# ServoBoard.net
KiCad netlist of a schematic drawn in EAGLE
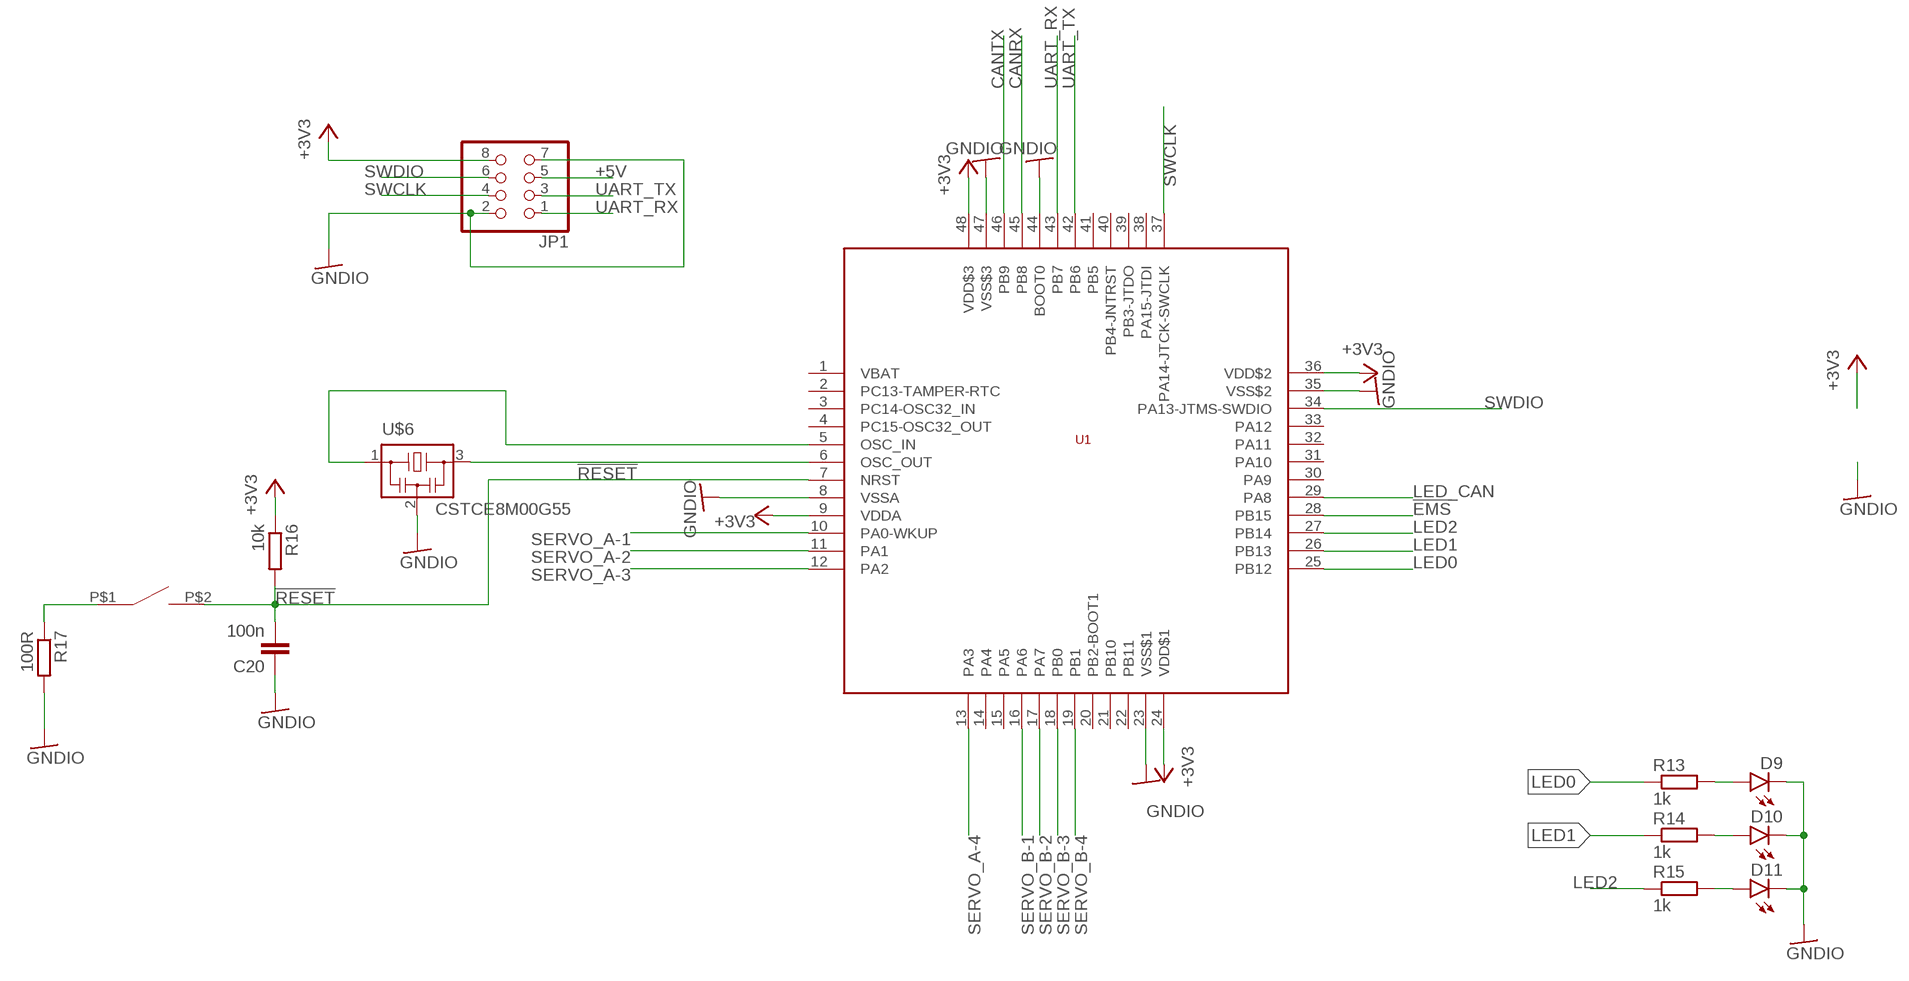
[diagram p0: schematic, sheet 1]
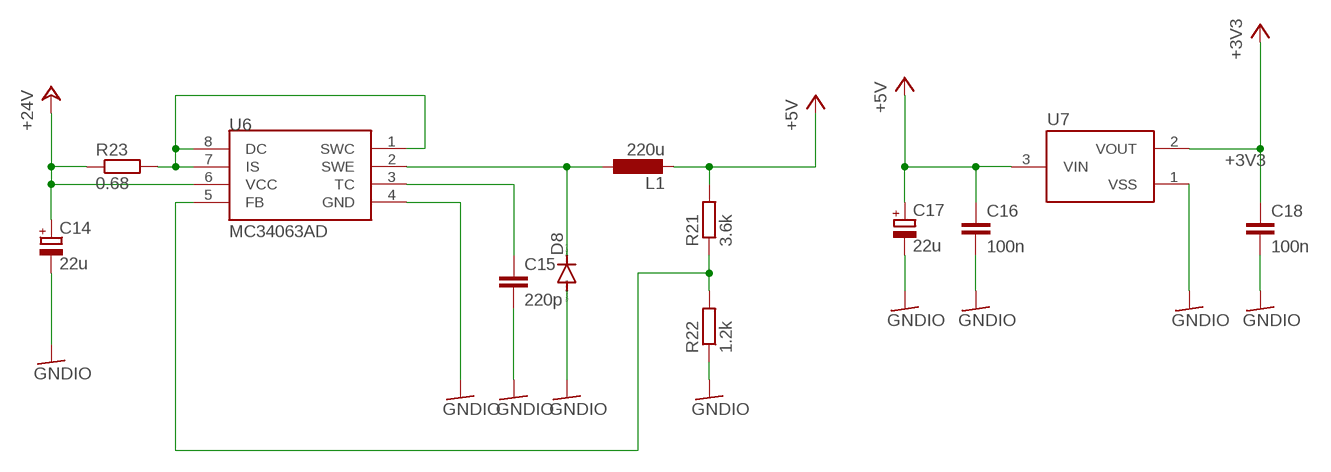
[diagram p1: schematic, sheet 2]
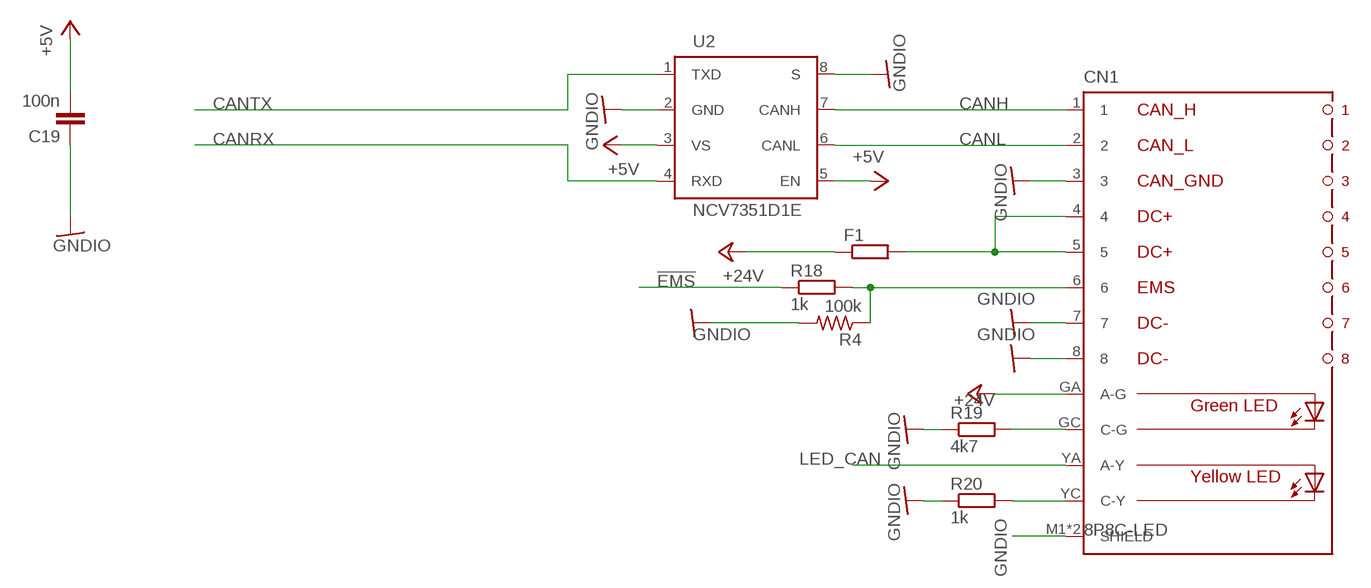
[diagram p2: schematic, sheet 3]
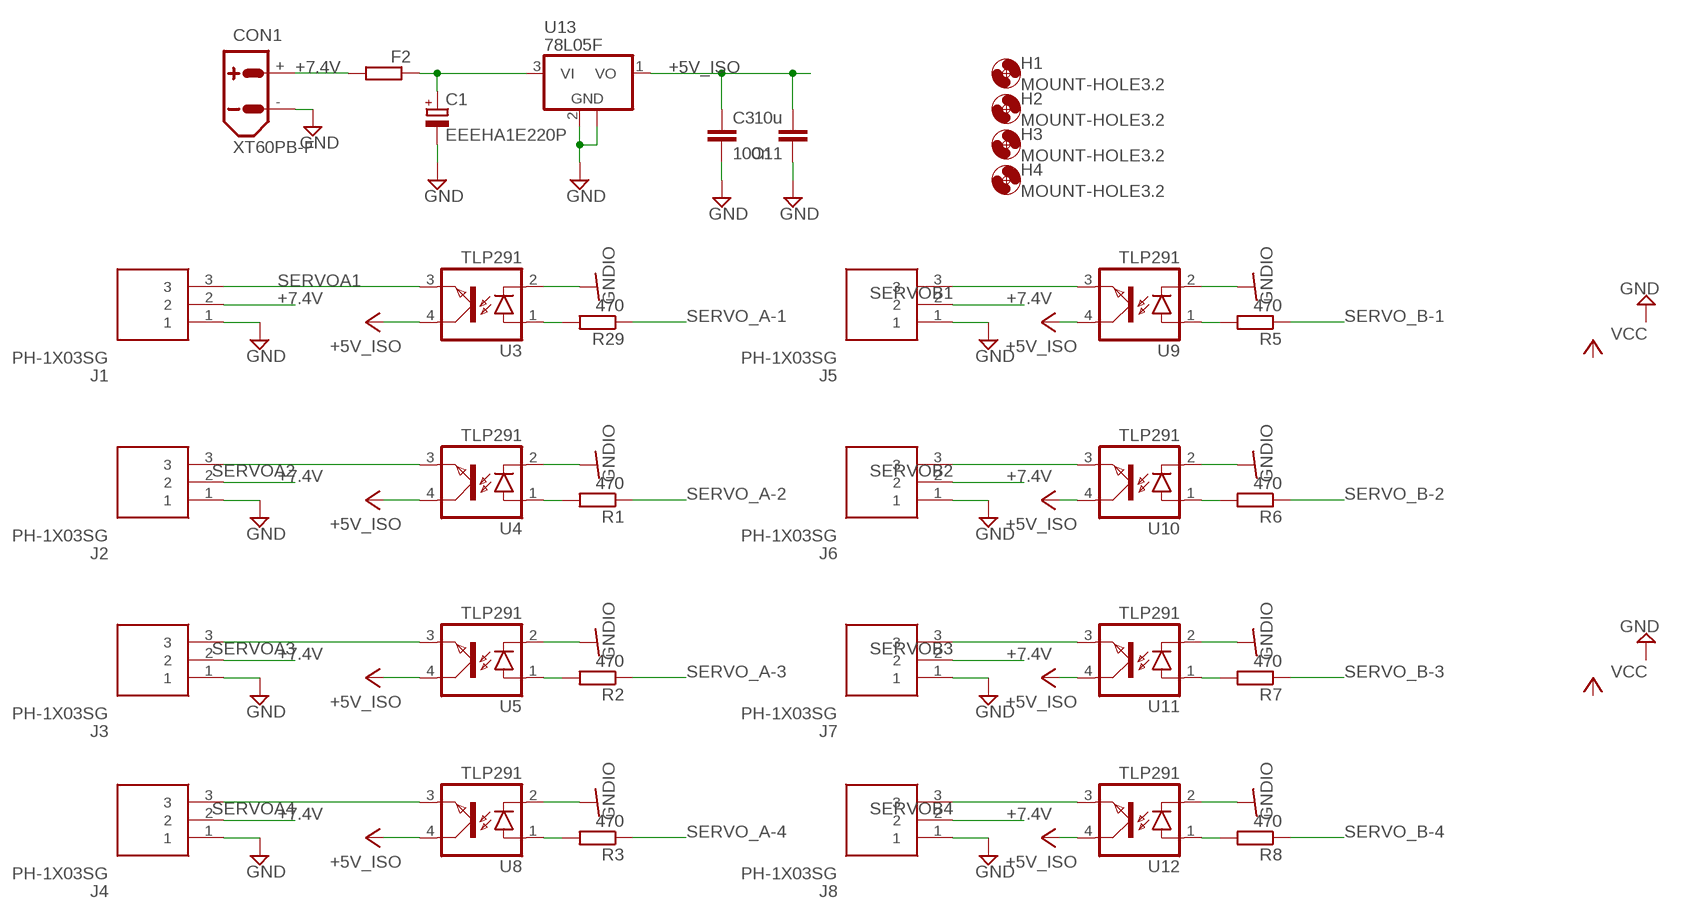
[diagram p3: schematic, sheet 4]

(export (version "E")
  (design (tool "Eeschema 10.0.6"))
  (components
    (comp (ref "C20")
      (value "100n")
      (footprint "eagle-import:C0603")
      (libsource (lib "eagle-import") (part "C-EUC0603"))
    )
    (comp (ref "D9")
      (value "LEDCHIPLED_0805")
      (footprint "eagle-import:CHIPLED_0805")
      (libsource (lib "eagle-import") (part "LEDCHIPLED_0805"))
    )
    (comp (ref "D10")
      (value "LEDCHIPLED_0805")
      (footprint "eagle-import:CHIPLED_0805")
      (libsource (lib "eagle-import") (part "LEDCHIPLED_0805"))
    )
    (comp (ref "D11")
      (value "LEDCHIPLED_0805")
      (footprint "eagle-import:CHIPLED_0805")
      (libsource (lib "eagle-import") (part "LEDCHIPLED_0805"))
    )
    (comp (ref "JP1")
      (value "PINHD-2X4")
      (footprint "eagle-import:2X04")
      (libsource (lib "eagle-import") (part "PINHD-2X4"))
    )
    (comp (ref "R13")
      (value "1k")
      (footprint "eagle-import:R0603")
      (libsource (lib "eagle-import") (part "R-EU_R0603"))
    )
    (comp (ref "R14")
      (value "1k")
      (footprint "eagle-import:R0603")
      (libsource (lib "eagle-import") (part "R-EU_R0603"))
    )
    (comp (ref "R15")
      (value "1k")
      (footprint "eagle-import:R0603")
      (libsource (lib "eagle-import") (part "R-EU_R0603"))
    )
    (comp (ref "R16")
      (value "10k")
      (footprint "eagle-import:R0603")
      (libsource (lib "eagle-import") (part "R-EU_R0603"))
    )
    (comp (ref "R17")
      (value "100R")
      (footprint "eagle-import:R0603")
      (libsource (lib "eagle-import") (part "R-EU_R0603"))
    )
    (comp (ref "SW1")
      (value "SWITCH_TACTILETOP")
      (footprint "eagle-import:SWITCH_TACTILE_3X6")
      (libsource (lib "eagle-import") (part "SWITCH_TACTILETOP"))
    )
    (comp (ref "U$6")
      (value "CSTCE8M00G55")
      (footprint "eagle-import:CSTCE8M00G55")
      (libsource (lib "eagle-import") (part "CSTCE8M00G55"))
    )
    (comp (ref "U1")
      (value "STM32F103C8")
      (footprint "eagle-import:LQFP48")
      (libsource (lib "eagle-import") (part "STM32F103C8"))
    )
    (comp (ref "C19")
      (value "100n")
      (footprint "eagle-import:C0603")
      (libsource (lib "eagle-import") (part "C-EUC0603"))
    )
    (comp (ref "CN1")
      (value "8P8C-LED")
      (footprint "eagle-import:8P8C-LED")
      (libsource (lib "eagle-import") (part "8P8C-LED"))
    )
    (comp (ref "F1")
      (value "R-EU_R1206")
      (footprint "eagle-import:R1206")
      (libsource (lib "eagle-import") (part "rcl_334_R-EU_R1206"))
    )
    (comp (ref "R4")
      (value "100k")
      (footprint "eagle-import:R0603")
      (libsource (lib "eagle-import") (part "R-US_R0603"))
    )
    (comp (ref "R18")
      (value "1k")
      (footprint "eagle-import:R0603")
      (libsource (lib "eagle-import") (part "rcl_334_R-EU_R0603"))
    )
    (comp (ref "R19")
      (value "4k7")
      (footprint "eagle-import:R0603")
      (libsource (lib "eagle-import") (part "rcl_334_R-EU_R0603"))
    )
    (comp (ref "R20")
      (value "1k")
      (footprint "eagle-import:R0603")
      (libsource (lib "eagle-import") (part "rcl_334_R-EU_R0603"))
    )
    (comp (ref "U2")
      (value "NCV7351D1E")
      (footprint "eagle-import:SO08")
      (libsource (lib "eagle-import") (part "NCV7351D1E"))
    )
    (comp (ref "C1")
      (value "EEEHA1E220P")
      (footprint "eagle-import:153CLV-0605")
      (libsource (lib "eagle-import") (part "rcl_334_CPOL-EU153CLV-0605"))
    )
    (comp (ref "C3")
      (value "100n")
      (footprint "eagle-import:C0603")
      (libsource (lib "eagle-import") (part "rcl_334_C-EUC0603"))
    )
    (comp (ref "C11")
      (value "10u")
      (footprint "eagle-import:C1210")
      (libsource (lib "eagle-import") (part "rcl_334_C-EUC1210"))
    )
    (comp (ref "CON1")
      (value "XT60PB-F")
      (footprint "eagle-import:XT60PB-F")
      (libsource (lib "eagle-import") (part "XT60PB-F"))
    )
    (comp (ref "F2")
      (value "R-EU_R1206")
      (footprint "eagle-import:R1206")
      (libsource (lib "eagle-import") (part "rcl_334_R-EU_R1206"))
    )
    (comp (ref "H1")
      (value "MOUNT-HOLE3.2")
      (footprint "eagle-import:3,2")
      (libsource (lib "eagle-import") (part "MOUNT-HOLE3.2"))
    )
    (comp (ref "H2")
      (value "MOUNT-HOLE3.2")
      (footprint "eagle-import:3,2")
      (libsource (lib "eagle-import") (part "MOUNT-HOLE3.2"))
    )
    (comp (ref "H3")
      (value "MOUNT-HOLE3.2")
      (footprint "eagle-import:3,2")
      (libsource (lib "eagle-import") (part "MOUNT-HOLE3.2"))
    )
    (comp (ref "H4")
      (value "MOUNT-HOLE3.2")
      (footprint "eagle-import:3,2")
      (libsource (lib "eagle-import") (part "MOUNT-HOLE3.2"))
    )
    (comp (ref "J1")
      (value "PH-1X03SG")
      (footprint "eagle-import:HDRV3W66P254_1X3_762X250X895P")
      (libsource (lib "eagle-import") (part "PH-1X03SG"))
    )
    (comp (ref "J2")
      (value "PH-1X03SG")
      (footprint "eagle-import:HDRV3W66P254_1X3_762X250X895P")
      (libsource (lib "eagle-import") (part "PH-1X03SG"))
    )
    (comp (ref "J3")
      (value "PH-1X03SG")
      (footprint "eagle-import:HDRV3W66P254_1X3_762X250X895P")
      (libsource (lib "eagle-import") (part "PH-1X03SG"))
    )
    (comp (ref "J4")
      (value "PH-1X03SG")
      (footprint "eagle-import:HDRV3W66P254_1X3_762X250X895P")
      (libsource (lib "eagle-import") (part "PH-1X03SG"))
    )
    (comp (ref "J5")
      (value "PH-1X03SG")
      (footprint "eagle-import:HDRV3W66P254_1X3_762X250X895P")
      (libsource (lib "eagle-import") (part "PH-1X03SG"))
    )
    (comp (ref "J6")
      (value "PH-1X03SG")
      (footprint "eagle-import:HDRV3W66P254_1X3_762X250X895P")
      (libsource (lib "eagle-import") (part "PH-1X03SG"))
    )
    (comp (ref "J7")
      (value "PH-1X03SG")
      (footprint "eagle-import:HDRV3W66P254_1X3_762X250X895P")
      (libsource (lib "eagle-import") (part "PH-1X03SG"))
    )
    (comp (ref "J8")
      (value "PH-1X03SG")
      (footprint "eagle-import:HDRV3W66P254_1X3_762X250X895P")
      (libsource (lib "eagle-import") (part "PH-1X03SG"))
    )
    (comp (ref "R1")
      (value "470")
      (footprint "eagle-import:R0603")
      (libsource (lib "eagle-import") (part "rcl_334_R-EU_R0603"))
    )
    (comp (ref "R2")
      (value "470")
      (footprint "eagle-import:R0603")
      (libsource (lib "eagle-import") (part "rcl_334_R-EU_R0603"))
    )
    (comp (ref "R3")
      (value "470")
      (footprint "eagle-import:R0603")
      (libsource (lib "eagle-import") (part "rcl_334_R-EU_R0603"))
    )
    (comp (ref "R5")
      (value "470")
      (footprint "eagle-import:R0603")
      (libsource (lib "eagle-import") (part "rcl_334_R-EU_R0603"))
    )
    (comp (ref "R6")
      (value "470")
      (footprint "eagle-import:R0603")
      (libsource (lib "eagle-import") (part "rcl_334_R-EU_R0603"))
    )
    (comp (ref "R7")
      (value "470")
      (footprint "eagle-import:R0603")
      (libsource (lib "eagle-import") (part "rcl_334_R-EU_R0603"))
    )
    (comp (ref "R8")
      (value "470")
      (footprint "eagle-import:R0603")
      (libsource (lib "eagle-import") (part "rcl_334_R-EU_R0603"))
    )
    (comp (ref "R29")
      (value "470")
      (footprint "eagle-import:R0603")
      (libsource (lib "eagle-import") (part "rcl_334_R-EU_R0603"))
    )
    (comp (ref "U3")
      (value "TLP291")
      (footprint "eagle-import:MINI-FLAT-4")
      (libsource (lib "eagle-import") (part "TLP291"))
    )
    (comp (ref "U4")
      (value "TLP291")
      (footprint "eagle-import:MINI-FLAT-4")
      (libsource (lib "eagle-import") (part "TLP291"))
    )
    (comp (ref "U5")
      (value "TLP291")
      (footprint "eagle-import:MINI-FLAT-4")
      (libsource (lib "eagle-import") (part "TLP291"))
    )
    (comp (ref "U8")
      (value "TLP291")
      (footprint "eagle-import:MINI-FLAT-4")
      (libsource (lib "eagle-import") (part "TLP291"))
    )
    (comp (ref "U9")
      (value "TLP291")
      (footprint "eagle-import:MINI-FLAT-4")
      (libsource (lib "eagle-import") (part "TLP291"))
    )
    (comp (ref "U10")
      (value "TLP291")
      (footprint "eagle-import:MINI-FLAT-4")
      (libsource (lib "eagle-import") (part "TLP291"))
    )
    (comp (ref "U11")
      (value "TLP291")
      (footprint "eagle-import:MINI-FLAT-4")
      (libsource (lib "eagle-import") (part "TLP291"))
    )
    (comp (ref "U12")
      (value "TLP291")
      (footprint "eagle-import:MINI-FLAT-4")
      (libsource (lib "eagle-import") (part "TLP291"))
    )
    (comp (ref "U13")
      (value "78L05F")
      (footprint "eagle-import:SOT89")
      (libsource (lib "eagle-import") (part "78LF05"))
    )
    (comp (ref "C14")
      (value "22u")
      (footprint "eagle-import:E2-5")
      (libsource (lib "eagle-import") (part "CPOL-EUE2-5"))
    )
    (comp (ref "C15")
      (value "220p")
      (footprint "eagle-import:C0603")
      (libsource (lib "eagle-import") (part "rcl_334_C-EUC0603"))
    )
    (comp (ref "C16")
      (value "100n")
      (footprint "eagle-import:C0603")
      (libsource (lib "eagle-import") (part "C-EUC0603"))
    )
    (comp (ref "C17")
      (value "22u")
      (footprint "eagle-import:E2-5")
      (libsource (lib "eagle-import") (part "CPOL-EUE2-5"))
    )
    (comp (ref "C18")
      (value "100n")
      (footprint "eagle-import:C0603")
      (libsource (lib "eagle-import") (part "C-EUC0603"))
    )
    (comp (ref "D8")
      (value "DIODE-SOD123")
      (footprint "eagle-import:SOD123")
      (libsource (lib "eagle-import") (part "DIODE-SOD123"))
    )
    (comp (ref "L1")
      (value "220u")
      (footprint "eagle-import:L5852")
      (libsource (lib "eagle-import") (part "L5852"))
    )
    (comp (ref "R21")
      (value "3.6k")
      (footprint "eagle-import:R0603")
      (libsource (lib "eagle-import") (part "rcl_334_R-EU_R0603"))
    )
    (comp (ref "R22")
      (value "1.2k")
      (footprint "eagle-import:R0603")
      (libsource (lib "eagle-import") (part "rcl_334_R-EU_R0603"))
    )
    (comp (ref "R23")
      (value "0.68")
      (footprint "eagle-import:R1206")
      (libsource (lib "eagle-import") (part "rcl_334_R-EU_R1206"))
    )
    (comp (ref "U6")
      (value "MC34063AD")
      (footprint "eagle-import:SOIC8")
      (libsource (lib "eagle-import") (part "MC34063AD"))
    )
    (comp (ref "U7")
      (value "XC6206")
      (footprint "eagle-import:SOT95P240X110-3")
      (libsource (lib "eagle-import") (part "XC6206"))
    )
  )
  (nets
    (net (code "1") (name "+3V3") (class "Default")
      (node (ref "C18") (pin "1") (pinfunction "1_1") (pintype "passive"))
      (node (ref "JP1") (pin "8") (pinfunction "8_8") (pintype "passive"))
      (node (ref "R16") (pin "1") (pinfunction "1_1") (pintype "passive"))
      (node (ref "U1") (pin "24") (pinfunction "VDD$1_24") (pintype "passive"))
      (node (ref "U1") (pin "36") (pinfunction "VDD$2_36") (pintype "passive"))
      (node (ref "U1") (pin "48") (pinfunction "VDD$3_48") (pintype "passive"))
      (node (ref "U1") (pin "9") (pinfunction "VDDA_9") (pintype "bidirectional"))
      (node (ref "U7") (pin "2") (pinfunction "VOUT_2") (pintype "bidirectional"))
    )
    (net (code "2") (name "+5V") (class "Default")
      (node (ref "C16") (pin "1") (pinfunction "1_1") (pintype "passive"))
      (node (ref "C17") (pin "+") (pinfunction "+_+") (pintype "passive"))
      (node (ref "C19") (pin "2") (pinfunction "2_2") (pintype "passive"))
      (node (ref "JP1") (pin "5") (pinfunction "5_5") (pintype "passive"))
      (node (ref "L1") (pin "P$2") (pinfunction "2_P$2") (pintype "passive"))
      (node (ref "R21") (pin "2") (pinfunction "2_2") (pintype "passive"))
      (node (ref "U2") (pin "3") (pinfunction "VS_3") (pintype "power_in"))
      (node (ref "U2") (pin "5") (pinfunction "EN_5") (pintype "input"))
      (node (ref "U7") (pin "3") (pinfunction "VIN_3") (pintype "bidirectional"))
    )
    (net (code "3") (name "+5V_ISO") (class "Default")
      (node (ref "C11") (pin "2") (pinfunction "2_2") (pintype "passive"))
      (node (ref "C3") (pin "1") (pinfunction "1_1") (pintype "passive"))
      (node (ref "U10") (pin "4") (pinfunction "COL_4") (pintype "passive"))
      (node (ref "U11") (pin "4") (pinfunction "COL_4") (pintype "passive"))
      (node (ref "U12") (pin "4") (pinfunction "COL_4") (pintype "passive"))
      (node (ref "U13") (pin "1") (pinfunction "VO_1") (pintype "passive"))
      (node (ref "U3") (pin "4") (pinfunction "COL_4") (pintype "passive"))
      (node (ref "U4") (pin "4") (pinfunction "COL_4") (pintype "passive"))
      (node (ref "U5") (pin "4") (pinfunction "COL_4") (pintype "passive"))
      (node (ref "U8") (pin "4") (pinfunction "COL_4") (pintype "passive"))
      (node (ref "U9") (pin "4") (pinfunction "COL_4") (pintype "passive"))
    )
    (net (code "4") (name "+7.4V") (class "Default")
      (node (ref "CON1") (pin "+") (pinfunction "+_+") (pintype "power_in"))
      (node (ref "F2") (pin "2") (pinfunction "2_2") (pintype "passive"))
      (node (ref "J1") (pin "2") (pinfunction "2_2") (pintype "bidirectional"))
      (node (ref "J2") (pin "2") (pinfunction "2_2") (pintype "bidirectional"))
      (node (ref "J3") (pin "2") (pinfunction "2_2") (pintype "bidirectional"))
      (node (ref "J4") (pin "2") (pinfunction "2_2") (pintype "bidirectional"))
      (node (ref "J5") (pin "2") (pinfunction "2_2") (pintype "bidirectional"))
      (node (ref "J6") (pin "2") (pinfunction "2_2") (pintype "bidirectional"))
      (node (ref "J7") (pin "2") (pinfunction "2_2") (pintype "bidirectional"))
      (node (ref "J8") (pin "2") (pinfunction "2_2") (pintype "bidirectional"))
    )
    (net (code "5") (name "+24V") (class "Default")
      (node (ref "C14") (pin "+") (pinfunction "+_+") (pintype "passive"))
      (node (ref "CN1") (pin "GA") (pinfunction "A-G_GA") (pintype "passive"))
      (node (ref "F1") (pin "1") (pinfunction "1_1") (pintype "passive"))
      (node (ref "R23") (pin "1") (pinfunction "1_1") (pintype "passive"))
      (node (ref "U6") (pin "6") (pinfunction "VCC_6") (pintype "passive"))
    )
    (net (code "6") (name "CANH") (class "Default")
      (node (ref "CN1") (pin "1") (pinfunction "1_1") (pintype "input"))
      (node (ref "U2") (pin "7") (pinfunction "CANH_7") (pintype "output"))
    )
    (net (code "7") (name "CANL") (class "Default")
      (node (ref "CN1") (pin "2") (pinfunction "2_2") (pintype "input"))
      (node (ref "U2") (pin "6") (pinfunction "CANL_6") (pintype "output"))
    )
    (net (code "8") (name "CANRX") (class "Default")
      (node (ref "U1") (pin "45") (pinfunction "PB8_45") (pintype "bidirectional"))
      (node (ref "U2") (pin "4") (pinfunction "RXD_4") (pintype "output"))
    )
    (net (code "9") (name "CANTX") (class "Default")
      (node (ref "U1") (pin "46") (pinfunction "PB9_46") (pintype "bidirectional"))
      (node (ref "U2") (pin "1") (pinfunction "TXD_1") (pintype "input"))
    )
    (net (code "10") (name "GND") (class "Default")
      (node (ref "C1") (pin "-") (pinfunction "-_-") (pintype "passive"))
      (node (ref "C11") (pin "1") (pinfunction "1_1") (pintype "passive"))
      (node (ref "C3") (pin "2") (pinfunction "2_2") (pintype "passive"))
      (node (ref "CON1") (pin "-") (pinfunction "-_-") (pintype "power_in"))
      (node (ref "J1") (pin "1") (pinfunction "1_1") (pintype "bidirectional"))
      (node (ref "J2") (pin "1") (pinfunction "1_1") (pintype "bidirectional"))
      (node (ref "J3") (pin "1") (pinfunction "1_1") (pintype "bidirectional"))
      (node (ref "J4") (pin "1") (pinfunction "1_1") (pintype "bidirectional"))
      (node (ref "J5") (pin "1") (pinfunction "1_1") (pintype "bidirectional"))
      (node (ref "J6") (pin "1") (pinfunction "1_1") (pintype "bidirectional"))
      (node (ref "J7") (pin "1") (pinfunction "1_1") (pintype "bidirectional"))
      (node (ref "J8") (pin "1") (pinfunction "1_1") (pintype "bidirectional"))
      (node (ref "U13") (pin "2") (pinfunction "GND_2") (pintype "passive"))
      (node (ref "U13") (pin "2@1") (pinfunction "GND_2@1") (pintype "passive"))
    )
    (net (code "11") (name "GNDIO") (class "Default")
      (node (ref "C14") (pin "-") (pinfunction "-_-") (pintype "passive"))
      (node (ref "C15") (pin "2") (pinfunction "2_2") (pintype "passive"))
      (node (ref "C16") (pin "2") (pinfunction "2_2") (pintype "passive"))
      (node (ref "C17") (pin "-") (pinfunction "-_-") (pintype "passive"))
      (node (ref "C18") (pin "2") (pinfunction "2_2") (pintype "passive"))
      (node (ref "C19") (pin "1") (pinfunction "1_1") (pintype "passive"))
      (node (ref "C20") (pin "1") (pinfunction "1_1") (pintype "passive"))
      (node (ref "CN1") (pin "3") (pinfunction "3_3") (pintype "input"))
      (node (ref "CN1") (pin "7") (pinfunction "7_7") (pintype "input"))
      (node (ref "CN1") (pin "8") (pinfunction "8_8") (pintype "input"))
      (node (ref "CN1") (pin "M1") (pinfunction "SHIELD_M1") (pintype "passive"))
      (node (ref "CN1") (pin "M2") (pinfunction "SHIELD_M2") (pintype "passive"))
      (node (ref "D10") (pin "C") (pinfunction "C_C") (pintype "passive"))
      (node (ref "D11") (pin "C") (pinfunction "C_C") (pintype "passive"))
      (node (ref "D8") (pin "A") (pinfunction "A_A") (pintype "passive"))
      (node (ref "D9") (pin "C") (pinfunction "C_C") (pintype "passive"))
      (node (ref "JP1") (pin "2") (pinfunction "2_2") (pintype "passive"))
      (node (ref "JP1") (pin "7") (pinfunction "7_7") (pintype "passive"))
      (node (ref "R17") (pin "2") (pinfunction "2_2") (pintype "passive"))
      (node (ref "R19") (pin "1") (pinfunction "1_1") (pintype "passive"))
      (node (ref "R20") (pin "1") (pinfunction "1_1") (pintype "passive"))
      (node (ref "R22") (pin "1") (pinfunction "1_1") (pintype "passive"))
      (node (ref "R4") (pin "2") (pinfunction "2_2") (pintype "passive"))
      (node (ref "U$6") (pin "2") (pinfunction "2_2") (pintype "passive"))
      (node (ref "U1") (pin "23") (pinfunction "VSS$1_23") (pintype "passive"))
      (node (ref "U1") (pin "35") (pinfunction "VSS$2_35") (pintype "passive"))
      (node (ref "U1") (pin "44") (pinfunction "BOOT0_44") (pintype "input"))
      (node (ref "U1") (pin "47") (pinfunction "VSS$3_47") (pintype "passive"))
      (node (ref "U1") (pin "8") (pinfunction "VSSA_8") (pintype "bidirectional"))
      (node (ref "U10") (pin "2") (pinfunction "C_2") (pintype "passive"))
      (node (ref "U11") (pin "2") (pinfunction "C_2") (pintype "passive"))
      (node (ref "U12") (pin "2") (pinfunction "C_2") (pintype "passive"))
      (node (ref "U2") (pin "2") (pinfunction "GND_2") (pintype "power_in"))
      (node (ref "U2") (pin "8") (pinfunction "S_8") (pintype "input"))
      (node (ref "U3") (pin "2") (pinfunction "C_2") (pintype "passive"))
      (node (ref "U4") (pin "2") (pinfunction "C_2") (pintype "passive"))
      (node (ref "U5") (pin "2") (pinfunction "C_2") (pintype "passive"))
      (node (ref "U6") (pin "4") (pinfunction "GND_4") (pintype "passive"))
      (node (ref "U7") (pin "1") (pinfunction "VSS_1") (pintype "bidirectional"))
      (node (ref "U8") (pin "2") (pinfunction "C_2") (pintype "passive"))
      (node (ref "U9") (pin "2") (pinfunction "C_2") (pintype "passive"))
    )
    (net (code "12") (name "LED0") (class "Default")
      (node (ref "R13") (pin "1") (pinfunction "1_1") (pintype "passive"))
      (node (ref "U1") (pin "25") (pinfunction "PB12_25") (pintype "bidirectional"))
    )
    (net (code "13") (name "LED1") (class "Default")
      (node (ref "R14") (pin "1") (pinfunction "1_1") (pintype "passive"))
      (node (ref "U1") (pin "26") (pinfunction "PB13_26") (pintype "bidirectional"))
    )
    (net (code "14") (name "LED2") (class "Default")
      (node (ref "R15") (pin "1") (pinfunction "1_1") (pintype "passive"))
      (node (ref "U1") (pin "27") (pinfunction "PB14_27") (pintype "bidirectional"))
    )
    (net (code "15") (name "LED_CAN") (class "Default")
      (node (ref "CN1") (pin "YA") (pinfunction "A-Y_YA") (pintype "passive"))
      (node (ref "U1") (pin "29") (pinfunction "PA8_29") (pintype "bidirectional"))
    )
    (net (code "16") (name "Net-(CN1-C-G)") (class "Default")
      (node (ref "CN1") (pin "GC") (pinfunction "C-G_GC") (pintype "passive"))
      (node (ref "R19") (pin "2") (pinfunction "2_2") (pintype "passive"))
    )
    (net (code "17") (name "Net-(CN1-C-Y)") (class "Default")
      (node (ref "CN1") (pin "YC") (pinfunction "C-Y_YC") (pintype "passive"))
      (node (ref "R20") (pin "2") (pinfunction "2_2") (pintype "passive"))
    )
    (net (code "18") (name "Net-(CN1-Pad4)") (class "Default")
      (node (ref "CN1") (pin "4") (pinfunction "4_4") (pintype "input"))
      (node (ref "CN1") (pin "5") (pinfunction "5_5") (pintype "input"))
      (node (ref "F1") (pin "2") (pinfunction "2_2") (pintype "passive"))
    )
    (net (code "19") (name "Net-(CN1-Pad6)") (class "Default")
      (node (ref "CN1") (pin "6") (pinfunction "6_6") (pintype "input"))
      (node (ref "R18") (pin "2") (pinfunction "2_2") (pintype "passive"))
      (node (ref "R4") (pin "1") (pinfunction "1_1") (pintype "passive"))
    )
    (net (code "20") (name "Net-(D9-PadA)") (class "Default")
      (node (ref "D9") (pin "A") (pinfunction "A_A") (pintype "passive"))
      (node (ref "R13") (pin "2") (pinfunction "2_2") (pintype "passive"))
    )
    (net (code "21") (name "Net-(D10-PadA)") (class "Default")
      (node (ref "D10") (pin "A") (pinfunction "A_A") (pintype "passive"))
      (node (ref "R14") (pin "2") (pinfunction "2_2") (pintype "passive"))
    )
    (net (code "22") (name "Net-(D11-PadA)") (class "Default")
      (node (ref "D11") (pin "A") (pinfunction "A_A") (pintype "passive"))
      (node (ref "R15") (pin "2") (pinfunction "2_2") (pintype "passive"))
    )
    (net (code "23") (name "Net-(L1-1)") (class "Default")
      (node (ref "D8") (pin "C") (pinfunction "C_C") (pintype "passive"))
      (node (ref "L1") (pin "P$1") (pinfunction "1_P$1") (pintype "passive"))
      (node (ref "U6") (pin "2") (pinfunction "SWE_2") (pintype "passive"))
    )
    (net (code "24") (name "Net-(SW1-1)") (class "Default")
      (node (ref "R17") (pin "1") (pinfunction "1_1") (pintype "passive"))
      (node (ref "SW1") (pin "P$1") (pinfunction "1_P$1") (pintype "bidirectional"))
    )
    (net (code "25") (name "Net-(U1-OSC_IN)") (class "Default")
      (node (ref "U$6") (pin "1") (pinfunction "1_1") (pintype "passive"))
      (node (ref "U1") (pin "5") (pinfunction "OSC_IN_5") (pintype "input"))
    )
    (net (code "26") (name "Net-(U1-OSC_OUT)") (class "Default")
      (node (ref "U$6") (pin "3") (pinfunction "3_3") (pintype "passive"))
      (node (ref "U1") (pin "6") (pinfunction "OSC_OUT_6") (pintype "output"))
    )
    (net (code "27") (name "Net-(U3-A)") (class "Default")
      (node (ref "R29") (pin "2") (pinfunction "2_2") (pintype "passive"))
      (node (ref "U3") (pin "1") (pinfunction "A_1") (pintype "passive"))
    )
    (net (code "28") (name "Net-(U4-A)") (class "Default")
      (node (ref "R1") (pin "2") (pinfunction "2_2") (pintype "passive"))
      (node (ref "U4") (pin "1") (pinfunction "A_1") (pintype "passive"))
    )
    (net (code "29") (name "Net-(U5-A)") (class "Default")
      (node (ref "R2") (pin "2") (pinfunction "2_2") (pintype "passive"))
      (node (ref "U5") (pin "1") (pinfunction "A_1") (pintype "passive"))
    )
    (net (code "30") (name "Net-(U6-DC)") (class "Default")
      (node (ref "R23") (pin "2") (pinfunction "2_2") (pintype "passive"))
      (node (ref "U6") (pin "1") (pinfunction "SWC_1") (pintype "passive"))
      (node (ref "U6") (pin "7") (pinfunction "IS_7") (pintype "passive"))
      (node (ref "U6") (pin "8") (pinfunction "DC_8") (pintype "passive"))
    )
    (net (code "31") (name "Net-(U6-FB)") (class "Default")
      (node (ref "R21") (pin "1") (pinfunction "1_1") (pintype "passive"))
      (node (ref "R22") (pin "2") (pinfunction "2_2") (pintype "passive"))
      (node (ref "U6") (pin "5") (pinfunction "FB_5") (pintype "passive"))
    )
    (net (code "32") (name "Net-(U6-TC)") (class "Default")
      (node (ref "C15") (pin "1") (pinfunction "1_1") (pintype "passive"))
      (node (ref "U6") (pin "3") (pinfunction "TC_3") (pintype "passive"))
    )
    (net (code "33") (name "Net-(U8-A)") (class "Default")
      (node (ref "R3") (pin "2") (pinfunction "2_2") (pintype "passive"))
      (node (ref "U8") (pin "1") (pinfunction "A_1") (pintype "passive"))
    )
    (net (code "34") (name "Net-(U9-A)") (class "Default")
      (node (ref "R5") (pin "2") (pinfunction "2_2") (pintype "passive"))
      (node (ref "U9") (pin "1") (pinfunction "A_1") (pintype "passive"))
    )
    (net (code "35") (name "Net-(U10-A)") (class "Default")
      (node (ref "R6") (pin "2") (pinfunction "2_2") (pintype "passive"))
      (node (ref "U10") (pin "1") (pinfunction "A_1") (pintype "passive"))
    )
    (net (code "36") (name "Net-(U11-A)") (class "Default")
      (node (ref "R7") (pin "2") (pinfunction "2_2") (pintype "passive"))
      (node (ref "U11") (pin "1") (pinfunction "A_1") (pintype "passive"))
    )
    (net (code "37") (name "Net-(U12-A)") (class "Default")
      (node (ref "R8") (pin "2") (pinfunction "2_2") (pintype "passive"))
      (node (ref "U12") (pin "1") (pinfunction "A_1") (pintype "passive"))
    )
    (net (code "38") (name "Net-(U13-VI)") (class "Default")
      (node (ref "C1") (pin "+") (pinfunction "+_+") (pintype "passive"))
      (node (ref "F2") (pin "1") (pinfunction "1_1") (pintype "passive"))
      (node (ref "U13") (pin "3") (pinfunction "VI_3") (pintype "input"))
    )
    (net (code "39") (name "SERVOA1") (class "Default")
      (node (ref "J1") (pin "3") (pinfunction "3_3") (pintype "bidirectional"))
      (node (ref "U3") (pin "3") (pinfunction "EMIT_3") (pintype "passive"))
    )
    (net (code "40") (name "SERVOA2") (class "Default")
      (node (ref "J2") (pin "3") (pinfunction "3_3") (pintype "bidirectional"))
      (node (ref "U4") (pin "3") (pinfunction "EMIT_3") (pintype "passive"))
    )
    (net (code "41") (name "SERVOA3") (class "Default")
      (node (ref "J3") (pin "3") (pinfunction "3_3") (pintype "bidirectional"))
      (node (ref "U5") (pin "3") (pinfunction "EMIT_3") (pintype "passive"))
    )
    (net (code "42") (name "SERVOA4") (class "Default")
      (node (ref "J4") (pin "3") (pinfunction "3_3") (pintype "bidirectional"))
      (node (ref "U8") (pin "3") (pinfunction "EMIT_3") (pintype "passive"))
    )
    (net (code "43") (name "SERVOB1") (class "Default")
      (node (ref "J5") (pin "3") (pinfunction "3_3") (pintype "bidirectional"))
      (node (ref "U9") (pin "3") (pinfunction "EMIT_3") (pintype "passive"))
    )
    (net (code "44") (name "SERVOB2") (class "Default")
      (node (ref "J6") (pin "3") (pinfunction "3_3") (pintype "bidirectional"))
      (node (ref "U10") (pin "3") (pinfunction "EMIT_3") (pintype "passive"))
    )
    (net (code "45") (name "SERVOB3") (class "Default")
      (node (ref "J7") (pin "3") (pinfunction "3_3") (pintype "bidirectional"))
      (node (ref "U11") (pin "3") (pinfunction "EMIT_3") (pintype "passive"))
    )
    (net (code "46") (name "SERVOB4") (class "Default")
      (node (ref "J8") (pin "3") (pinfunction "3_3") (pintype "bidirectional"))
      (node (ref "U12") (pin "3") (pinfunction "EMIT_3") (pintype "passive"))
    )
    (net (code "47") (name "SERVO_A-1") (class "Default")
      (node (ref "R29") (pin "1") (pinfunction "1_1") (pintype "passive"))
      (node (ref "U1") (pin "10") (pinfunction "PA0-WKUP_10") (pintype "bidirectional"))
    )
    (net (code "48") (name "SERVO_A-2") (class "Default")
      (node (ref "R1") (pin "1") (pinfunction "1_1") (pintype "passive"))
      (node (ref "U1") (pin "11") (pinfunction "PA1_11") (pintype "bidirectional"))
    )
    (net (code "49") (name "SERVO_A-3") (class "Default")
      (node (ref "R2") (pin "1") (pinfunction "1_1") (pintype "passive"))
      (node (ref "U1") (pin "12") (pinfunction "PA2_12") (pintype "bidirectional"))
    )
    (net (code "50") (name "SERVO_A-4") (class "Default")
      (node (ref "R3") (pin "1") (pinfunction "1_1") (pintype "passive"))
      (node (ref "U1") (pin "13") (pinfunction "PA3_13") (pintype "bidirectional"))
    )
    (net (code "51") (name "SERVO_B-1") (class "Default")
      (node (ref "R5") (pin "1") (pinfunction "1_1") (pintype "passive"))
      (node (ref "U1") (pin "16") (pinfunction "PA6_16") (pintype "bidirectional"))
    )
    (net (code "52") (name "SERVO_B-2") (class "Default")
      (node (ref "R6") (pin "1") (pinfunction "1_1") (pintype "passive"))
      (node (ref "U1") (pin "17") (pinfunction "PA7_17") (pintype "bidirectional"))
    )
    (net (code "53") (name "SERVO_B-3") (class "Default")
      (node (ref "R7") (pin "1") (pinfunction "1_1") (pintype "passive"))
      (node (ref "U1") (pin "18") (pinfunction "PB0_18") (pintype "bidirectional"))
    )
    (net (code "54") (name "SERVO_B-4") (class "Default")
      (node (ref "R8") (pin "1") (pinfunction "1_1") (pintype "passive"))
      (node (ref "U1") (pin "19") (pinfunction "PB1_19") (pintype "bidirectional"))
    )
    (net (code "55") (name "SWCLK") (class "Default")
      (node (ref "JP1") (pin "4") (pinfunction "4_4") (pintype "passive"))
      (node (ref "U1") (pin "37") (pinfunction "PA14-JTCK-SWCLK_37") (pintype "bidirectional"))
    )
    (net (code "56") (name "SWDIO") (class "Default")
      (node (ref "JP1") (pin "6") (pinfunction "6_6") (pintype "passive"))
      (node (ref "U1") (pin "34") (pinfunction "PA13-JTMS-SWDIO_34") (pintype "bidirectional"))
    )
    (net (code "57") (name "UART_RX") (class "Default")
      (node (ref "JP1") (pin "1") (pinfunction "1_1") (pintype "passive"))
      (node (ref "U1") (pin "43") (pinfunction "PB7_43") (pintype "bidirectional"))
    )
    (net (code "58") (name "UART_TX") (class "Default")
      (node (ref "JP1") (pin "3") (pinfunction "3_3") (pintype "passive"))
      (node (ref "U1") (pin "42") (pinfunction "PB6_42") (pintype "bidirectional"))
    )
    (net (code "60") (name "unconnected-(U1-PA4-Pad14)") (class "Default")
      (node (ref "U1") (pin "14") (pinfunction "PA4_14") (pintype "bidirectional"))
    )
    (net (code "61") (name "unconnected-(U1-PA5-Pad15)") (class "Default")
      (node (ref "U1") (pin "15") (pinfunction "PA5_15") (pintype "bidirectional"))
    )
    (net (code "62") (name "unconnected-(U1-PA9-Pad30)") (class "Default")
      (node (ref "U1") (pin "30") (pinfunction "PA9_30") (pintype "bidirectional"))
    )
    (net (code "63") (name "unconnected-(U1-PA10-Pad31)") (class "Default")
      (node (ref "U1") (pin "31") (pinfunction "PA10_31") (pintype "bidirectional"))
    )
    (net (code "64") (name "unconnected-(U1-PA11-Pad32)") (class "Default")
      (node (ref "U1") (pin "32") (pinfunction "PA11_32") (pintype "bidirectional"))
    )
    (net (code "65") (name "unconnected-(U1-PA12-Pad33)") (class "Default")
      (node (ref "U1") (pin "33") (pinfunction "PA12_33") (pintype "bidirectional"))
    )
    (net (code "66") (name "unconnected-(U1-PA15-JTDI-Pad38)") (class "Default")
      (node (ref "U1") (pin "38") (pinfunction "PA15-JTDI_38") (pintype "bidirectional"))
    )
    (net (code "67") (name "unconnected-(U1-PB2-BOOT1-Pad20)") (class "Default")
      (node (ref "U1") (pin "20") (pinfunction "PB2-BOOT1_20") (pintype "bidirectional"))
    )
    (net (code "68") (name "unconnected-(U1-PB3-JTDO-Pad39)") (class "Default")
      (node (ref "U1") (pin "39") (pinfunction "PB3-JTDO_39") (pintype "bidirectional"))
    )
    (net (code "69") (name "unconnected-(U1-PB4-JNTRST-Pad40)") (class "Default")
      (node (ref "U1") (pin "40") (pinfunction "PB4-JNTRST_40") (pintype "bidirectional"))
    )
    (net (code "70") (name "unconnected-(U1-PB5-Pad41)") (class "Default")
      (node (ref "U1") (pin "41") (pinfunction "PB5_41") (pintype "bidirectional"))
    )
    (net (code "71") (name "unconnected-(U1-PB10-Pad21)") (class "Default")
      (node (ref "U1") (pin "21") (pinfunction "PB10_21") (pintype "bidirectional"))
    )
    (net (code "72") (name "unconnected-(U1-PB11-Pad22)") (class "Default")
      (node (ref "U1") (pin "22") (pinfunction "PB11_22") (pintype "bidirectional"))
    )
    (net (code "73") (name "unconnected-(U1-PC13-TAMPER-RTC-Pad2)") (class "Default")
      (node (ref "U1") (pin "2") (pinfunction "PC13-TAMPER-RTC_2") (pintype "bidirectional"))
    )
    (net (code "74") (name "unconnected-(U1-PC14-OSC32_IN-Pad3)") (class "Default")
      (node (ref "U1") (pin "3") (pinfunction "PC14-OSC32_IN_3") (pintype "bidirectional"))
    )
    (net (code "75") (name "unconnected-(U1-PC15-OSC32_OUT-Pad4)") (class "Default")
      (node (ref "U1") (pin "4") (pinfunction "PC15-OSC32_OUT_4") (pintype "bidirectional"))
    )
    (net (code "76") (name "unconnected-(U1-VBAT-Pad1)") (class "Default")
      (node (ref "U1") (pin "1") (pinfunction "VBAT_1") (pintype "passive"))
    )
    (net (code "77") (name "~{EMS}") (class "Default")
      (node (ref "R18") (pin "1") (pinfunction "1_1") (pintype "passive"))
      (node (ref "U1") (pin "28") (pinfunction "PB15_28") (pintype "bidirectional"))
    )
    (net (code "78") (name "~{RESET}") (class "Default")
      (node (ref "C20") (pin "2") (pinfunction "2_2") (pintype "passive"))
      (node (ref "R16") (pin "2") (pinfunction "2_2") (pintype "passive"))
      (node (ref "SW1") (pin "P$2") (pinfunction "2_P$2") (pintype "bidirectional"))
      (node (ref "U1") (pin "7") (pinfunction "NRST_7") (pintype "bidirectional"))
    )
  )
)
